# duikboot.net
KiCad netlist of a schematic drawn in EAGLE
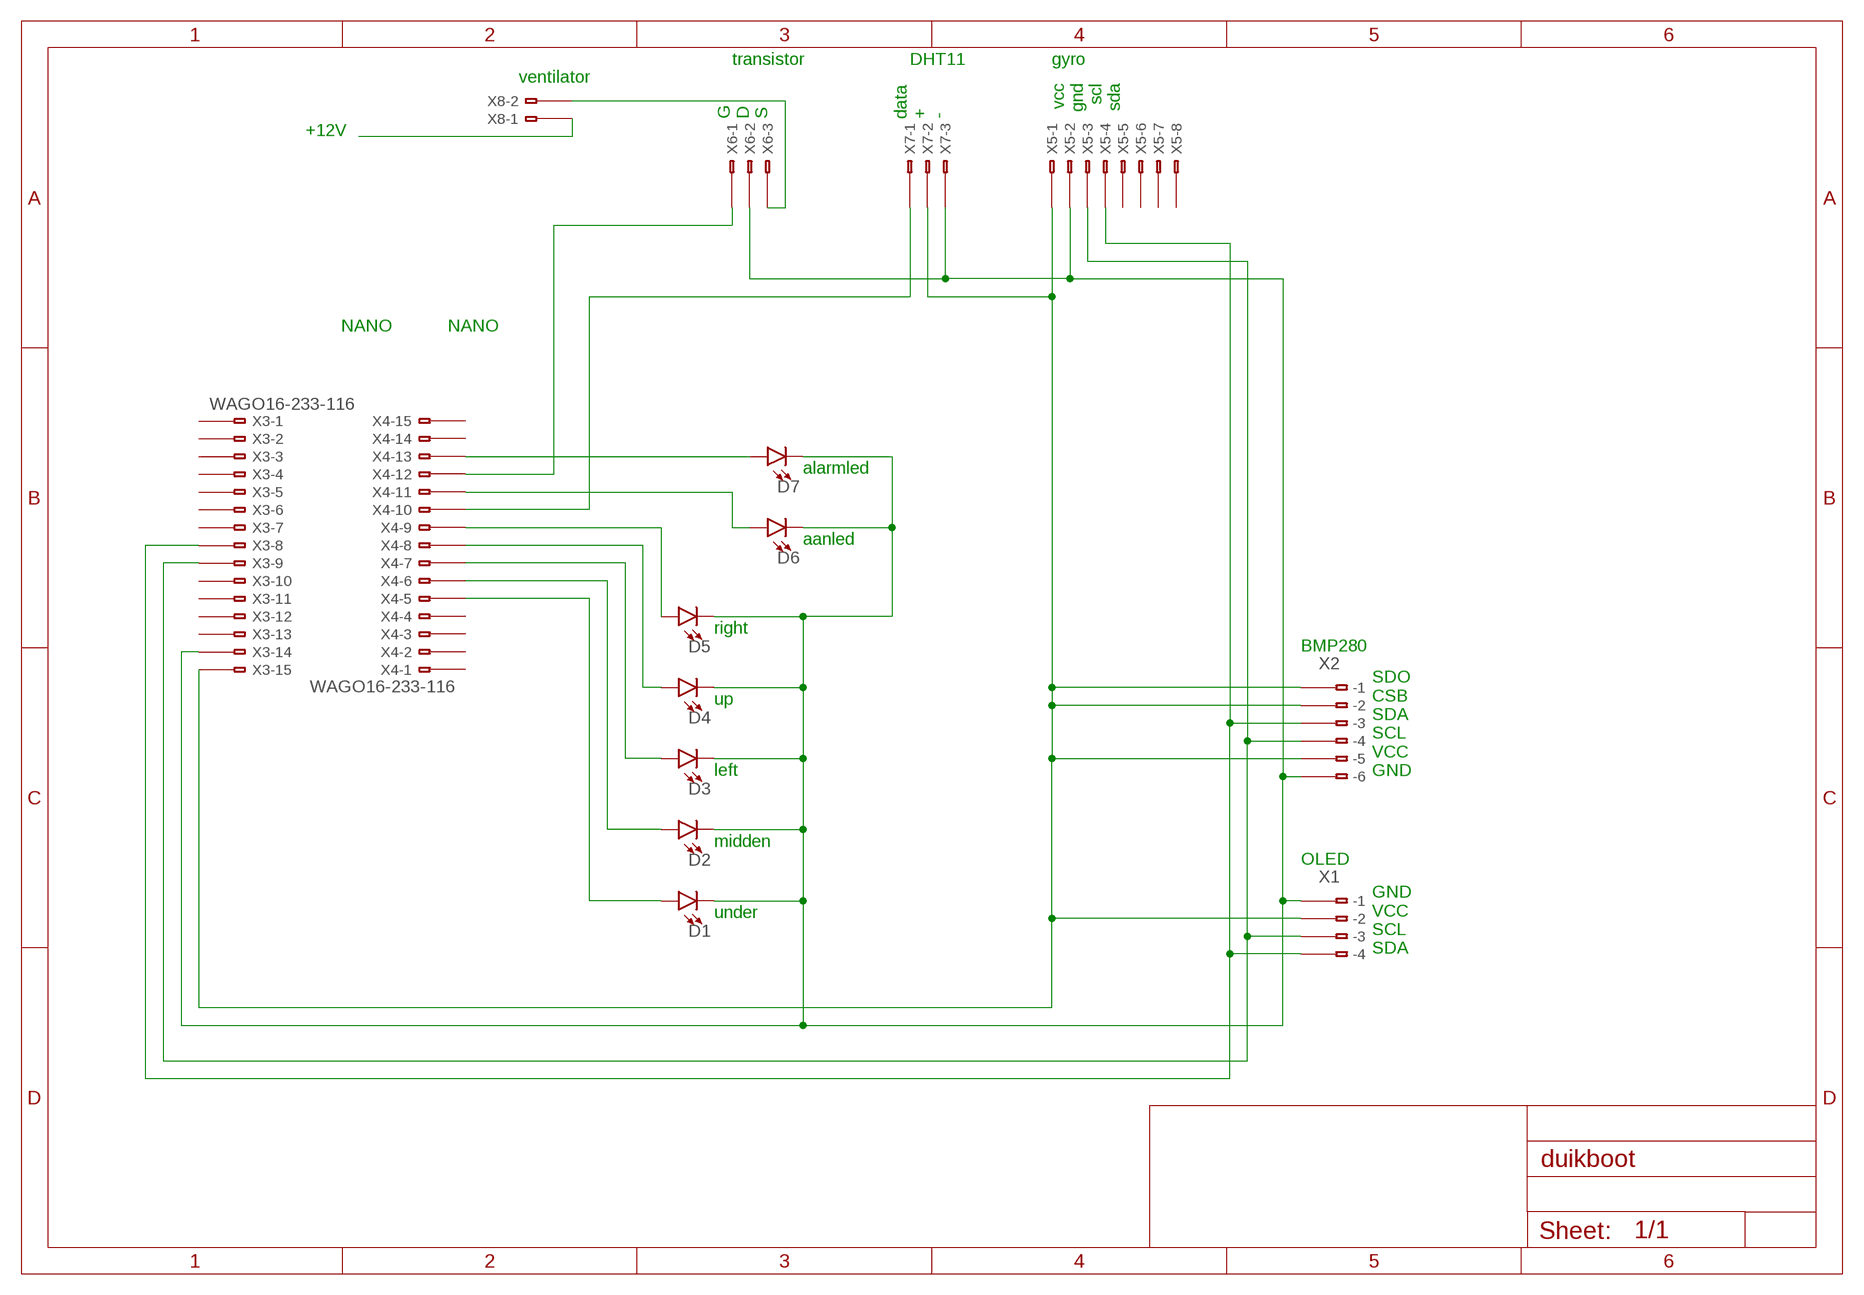
[diagram p0: schematic, sheet 1]

(export (version "E")
  (design (tool "Eeschema 10.0.6"))
  (components
    (comp (ref "D1")
      (value "LED5MM")
      (footprint "eagle-import:LED_5MM")
      (libsource (lib "eagle-import") (part "LED5MM"))
    )
    (comp (ref "D2")
      (value "LED5MM")
      (footprint "eagle-import:LED_5MM")
      (libsource (lib "eagle-import") (part "LED5MM"))
    )
    (comp (ref "D3")
      (value "LED5MM")
      (footprint "eagle-import:LED_5MM")
      (libsource (lib "eagle-import") (part "LED5MM"))
    )
    (comp (ref "D4")
      (value "LED5MM")
      (footprint "eagle-import:LED_5MM")
      (libsource (lib "eagle-import") (part "LED5MM"))
    )
    (comp (ref "D5")
      (value "LED5MM")
      (footprint "eagle-import:LED_5MM")
      (libsource (lib "eagle-import") (part "LED5MM"))
    )
    (comp (ref "D6")
      (value "LED5MM")
      (footprint "eagle-import:LED_5MM")
      (libsource (lib "eagle-import") (part "LED5MM"))
    )
    (comp (ref "D7")
      (value "LED5MM")
      (footprint "eagle-import:LED_5MM")
      (libsource (lib "eagle-import") (part "LED5MM"))
    )
    (comp (ref "X1")
      (value "233-104")
      (footprint "eagle-import:233-104")
      (libsource (lib "eagle-import") (part "233-104"))
    )
    (comp (ref "X2")
      (value "233-106")
      (footprint "eagle-import:233-106")
      (libsource (lib "eagle-import") (part "233-106"))
    )
    (comp (ref "X3")
      (value "WAGO16-233-116")
      (footprint "eagle-import:233-116")
      (fields (field (name "MPN") "233-116"))
      (libsource (lib "eagle-import") (part "WAGO16-233-116"))
    )
    (comp (ref "X4")
      (value "WAGO16-233-116")
      (footprint "eagle-import:233-116")
      (fields (field (name "MPN") "233-116"))
      (libsource (lib "eagle-import") (part "WAGO16-233-116"))
    )
    (comp (ref "X5")
      (value "WAGO16-233-116")
      (footprint "eagle-import:233-116")
      (fields (field (name "MPN") "233-116"))
      (libsource (lib "eagle-import") (part "WAGO16-233-116"))
    )
    (comp (ref "X6")
      (value "WAGO16-233-116")
      (footprint "eagle-import:233-116")
      (fields (field (name "MPN") "233-116"))
      (libsource (lib "eagle-import") (part "WAGO16-233-116"))
    )
    (comp (ref "X7")
      (value "WAGO16-233-116")
      (footprint "eagle-import:233-116")
      (fields (field (name "MPN") "233-116"))
      (libsource (lib "eagle-import") (part "WAGO16-233-116"))
    )
    (comp (ref "X8")
      (value "WAGO16-233-116")
      (footprint "eagle-import:233-116")
      (fields (field (name "MPN") "233-116"))
      (libsource (lib "eagle-import") (part "WAGO16-233-116"))
    )
  )
  (nets
    (net (code "1") (name "Net-(D1-C)") (class "Default")
      (node (ref "D1") (pin "K") (pinfunction "C_K") (pintype "passive"))
      (node (ref "D2") (pin "K") (pinfunction "C_K") (pintype "passive"))
      (node (ref "D3") (pin "K") (pinfunction "C_K") (pintype "passive"))
      (node (ref "D4") (pin "K") (pinfunction "C_K") (pintype "passive"))
      (node (ref "D5") (pin "K") (pinfunction "C_K") (pintype "passive"))
      (node (ref "D6") (pin "K") (pinfunction "C_K") (pintype "passive"))
      (node (ref "D7") (pin "K") (pinfunction "C_K") (pintype "passive"))
      (node (ref "X1") (pin "B1") (pinfunction "B-1_B1") (pintype "passive"))
      (node (ref "X2") (pin "B6") (pinfunction "B-6_B6") (pintype "passive"))
      (node (ref "X3") (pin "B14") (pinfunction "B1_B14") (pintype "passive"))
      (node (ref "X5") (pin "B2") (pinfunction "B1_B2") (pintype "passive"))
      (node (ref "X6") (pin "B2") (pinfunction "B1_B2") (pintype "passive"))
      (node (ref "X7") (pin "B3") (pinfunction "B1_B3") (pintype "passive"))
    )
    (net (code "2") (name "Net-(X1-B-2)") (class "Default")
      (node (ref "X1") (pin "B2") (pinfunction "B-2_B2") (pintype "passive"))
      (node (ref "X2") (pin "B1") (pinfunction "B-1_B1") (pintype "passive"))
      (node (ref "X2") (pin "B2") (pinfunction "B-2_B2") (pintype "passive"))
      (node (ref "X2") (pin "B5") (pinfunction "B-5_B5") (pintype "passive"))
      (node (ref "X3") (pin "B15") (pinfunction "B1_B15") (pintype "passive"))
      (node (ref "X5") (pin "B1") (pinfunction "B1_B1") (pintype "passive"))
      (node (ref "X7") (pin "B2") (pinfunction "B1_B2") (pintype "passive"))
    )
    (net (code "3") (name "Net-(X1-B-3)") (class "Default")
      (node (ref "X1") (pin "B3") (pinfunction "B-3_B3") (pintype "passive"))
      (node (ref "X2") (pin "B4") (pinfunction "B-4_B4") (pintype "passive"))
      (node (ref "X3") (pin "B9") (pinfunction "B1_B9") (pintype "passive"))
      (node (ref "X5") (pin "B3") (pinfunction "B1_B3") (pintype "passive"))
    )
    (net (code "4") (name "Net-(X1-B-4)") (class "Default")
      (node (ref "X1") (pin "B4") (pinfunction "B-4_B4") (pintype "passive"))
      (node (ref "X2") (pin "B3") (pinfunction "B-3_B3") (pintype "passive"))
      (node (ref "X3") (pin "B8") (pinfunction "B1_B8") (pintype "passive"))
      (node (ref "X5") (pin "B4") (pinfunction "B1_B4") (pintype "passive"))
    )
    (net (code "5") (name "Net-(X4B-B1)") (class "Default")
      (node (ref "X4") (pin "B10") (pinfunction "B1_B10") (pintype "passive"))
      (node (ref "X7") (pin "B1") (pinfunction "B1_B1") (pintype "passive"))
    )
    (net (code "6") (name "Net-(X4C-B1)") (class "Default")
      (node (ref "D6") (pin "A") (pinfunction "A_A") (pintype "passive"))
      (node (ref "X4") (pin "B11") (pinfunction "B1_B11") (pintype "passive"))
    )
    (net (code "7") (name "Net-(X4D-B1)") (class "Default")
      (node (ref "X4") (pin "B12") (pinfunction "B1_B12") (pintype "passive"))
      (node (ref "X6") (pin "B1") (pinfunction "B1_B1") (pintype "passive"))
    )
    (net (code "8") (name "Net-(X4E-B1)") (class "Default")
      (node (ref "D7") (pin "A") (pinfunction "A_A") (pintype "passive"))
      (node (ref "X4") (pin "B13") (pinfunction "B1_B13") (pintype "passive"))
    )
    (net (code "9") (name "Net-(X4L-B1)") (class "Default")
      (node (ref "D1") (pin "A") (pinfunction "A_A") (pintype "passive"))
      (node (ref "X4") (pin "B5") (pinfunction "B1_B5") (pintype "passive"))
    )
    (net (code "10") (name "Net-(X4M-B1)") (class "Default")
      (node (ref "D2") (pin "A") (pinfunction "A_A") (pintype "passive"))
      (node (ref "X4") (pin "B6") (pinfunction "B1_B6") (pintype "passive"))
    )
    (net (code "11") (name "Net-(X4N-B1)") (class "Default")
      (node (ref "D3") (pin "A") (pinfunction "A_A") (pintype "passive"))
      (node (ref "X4") (pin "B7") (pinfunction "B1_B7") (pintype "passive"))
    )
    (net (code "12") (name "Net-(X4O-B1)") (class "Default")
      (node (ref "D4") (pin "A") (pinfunction "A_A") (pintype "passive"))
      (node (ref "X4") (pin "B8") (pinfunction "B1_B8") (pintype "passive"))
    )
    (net (code "13") (name "Net-(X4P-B1)") (class "Default")
      (node (ref "D5") (pin "A") (pinfunction "A_A") (pintype "passive"))
      (node (ref "X4") (pin "B9") (pinfunction "B1_B9") (pintype "passive"))
    )
    (net (code "14") (name "Net-(X6J-B1)") (class "Default")
      (node (ref "X6") (pin "B3") (pinfunction "B1_B3") (pintype "passive"))
      (node (ref "X8") (pin "B2") (pinfunction "B1_B2") (pintype "passive"))
    )
    (net (code "15") (name "unconnected-(X1--1-PadA1)") (class "Default")
      (node (ref "X1") (pin "A1") (pinfunction "-1_A1") (pintype "passive"))
    )
    (net (code "16") (name "unconnected-(X1--2-PadA2)") (class "Default")
      (node (ref "X1") (pin "A2") (pinfunction "-2_A2") (pintype "passive"))
    )
    (net (code "17") (name "unconnected-(X1--3-PadA3)") (class "Default")
      (node (ref "X1") (pin "A3") (pinfunction "-3_A3") (pintype "passive"))
    )
    (net (code "18") (name "unconnected-(X1--4-PadA4)") (class "Default")
      (node (ref "X1") (pin "A4") (pinfunction "-4_A4") (pintype "passive"))
    )
    (net (code "19") (name "unconnected-(X2--1-PadA1)") (class "Default")
      (node (ref "X2") (pin "A1") (pinfunction "-1_A1") (pintype "passive"))
    )
    (net (code "20") (name "unconnected-(X2--2-PadA2)") (class "Default")
      (node (ref "X2") (pin "A2") (pinfunction "-2_A2") (pintype "passive"))
    )
    (net (code "21") (name "unconnected-(X2--3-PadA3)") (class "Default")
      (node (ref "X2") (pin "A3") (pinfunction "-3_A3") (pintype "passive"))
    )
    (net (code "22") (name "unconnected-(X2--4-PadA4)") (class "Default")
      (node (ref "X2") (pin "A4") (pinfunction "-4_A4") (pintype "passive"))
    )
    (net (code "23") (name "unconnected-(X2--5-PadA5)") (class "Default")
      (node (ref "X2") (pin "A5") (pinfunction "-5_A5") (pintype "passive"))
    )
    (net (code "24") (name "unconnected-(X2--6-PadA6)") (class "Default")
      (node (ref "X2") (pin "A6") (pinfunction "-6_A6") (pintype "passive"))
    )
    (net (code "25") (name "unconnected-(X3-PadA1)") (class "Default")
      (node (ref "X3") (pin "A1") (pinfunction "A1_A1") (pintype "passive"))
    )
    (net (code "26") (name "unconnected-(X3-PadB1)") (class "Default")
      (node (ref "X3") (pin "B1") (pinfunction "B1_B1") (pintype "passive"))
    )
    (net (code "27") (name "unconnected-(X3B-A1-PadA10)") (class "Default")
      (node (ref "X3") (pin "A10") (pinfunction "A1_A10") (pintype "passive"))
    )
    (net (code "28") (name "unconnected-(X3B-B1-PadB10)") (class "Default")
      (node (ref "X3") (pin "B10") (pinfunction "B1_B10") (pintype "passive"))
    )
    (net (code "29") (name "unconnected-(X3C-A1-PadA11)") (class "Default")
      (node (ref "X3") (pin "A11") (pinfunction "A1_A11") (pintype "passive"))
    )
    (net (code "30") (name "unconnected-(X3C-B1-PadB11)") (class "Default")
      (node (ref "X3") (pin "B11") (pinfunction "B1_B11") (pintype "passive"))
    )
    (net (code "31") (name "unconnected-(X3D-A1-PadA12)") (class "Default")
      (node (ref "X3") (pin "A12") (pinfunction "A1_A12") (pintype "passive"))
    )
    (net (code "32") (name "unconnected-(X3D-B1-PadB12)") (class "Default")
      (node (ref "X3") (pin "B12") (pinfunction "B1_B12") (pintype "passive"))
    )
    (net (code "33") (name "unconnected-(X3E-A1-PadA13)") (class "Default")
      (node (ref "X3") (pin "A13") (pinfunction "A1_A13") (pintype "passive"))
    )
    (net (code "34") (name "unconnected-(X3E-B1-PadB13)") (class "Default")
      (node (ref "X3") (pin "B13") (pinfunction "B1_B13") (pintype "passive"))
    )
    (net (code "35") (name "unconnected-(X3F-A1-PadA14)") (class "Default")
      (node (ref "X3") (pin "A14") (pinfunction "A1_A14") (pintype "passive"))
    )
    (net (code "36") (name "unconnected-(X3G-A1-PadA15)") (class "Default")
      (node (ref "X3") (pin "A15") (pinfunction "A1_A15") (pintype "passive"))
    )
    (net (code "37") (name "unconnected-(X3I-A1-PadA2)") (class "Default")
      (node (ref "X3") (pin "A2") (pinfunction "A1_A2") (pintype "passive"))
    )
    (net (code "38") (name "unconnected-(X3I-B1-PadB2)") (class "Default")
      (node (ref "X3") (pin "B2") (pinfunction "B1_B2") (pintype "passive"))
    )
    (net (code "39") (name "unconnected-(X3J-A1-PadA3)") (class "Default")
      (node (ref "X3") (pin "A3") (pinfunction "A1_A3") (pintype "passive"))
    )
    (net (code "40") (name "unconnected-(X3J-B1-PadB3)") (class "Default")
      (node (ref "X3") (pin "B3") (pinfunction "B1_B3") (pintype "passive"))
    )
    (net (code "41") (name "unconnected-(X3K-A1-PadA4)") (class "Default")
      (node (ref "X3") (pin "A4") (pinfunction "A1_A4") (pintype "passive"))
    )
    (net (code "42") (name "unconnected-(X3K-B1-PadB4)") (class "Default")
      (node (ref "X3") (pin "B4") (pinfunction "B1_B4") (pintype "passive"))
    )
    (net (code "43") (name "unconnected-(X3L-A1-PadA5)") (class "Default")
      (node (ref "X3") (pin "A5") (pinfunction "A1_A5") (pintype "passive"))
    )
    (net (code "44") (name "unconnected-(X3L-B1-PadB5)") (class "Default")
      (node (ref "X3") (pin "B5") (pinfunction "B1_B5") (pintype "passive"))
    )
    (net (code "45") (name "unconnected-(X3M-A1-PadA6)") (class "Default")
      (node (ref "X3") (pin "A6") (pinfunction "A1_A6") (pintype "passive"))
    )
    (net (code "46") (name "unconnected-(X3M-B1-PadB6)") (class "Default")
      (node (ref "X3") (pin "B6") (pinfunction "B1_B6") (pintype "passive"))
    )
    (net (code "47") (name "unconnected-(X3N-A1-PadA7)") (class "Default")
      (node (ref "X3") (pin "A7") (pinfunction "A1_A7") (pintype "passive"))
    )
    (net (code "48") (name "unconnected-(X3N-B1-PadB7)") (class "Default")
      (node (ref "X3") (pin "B7") (pinfunction "B1_B7") (pintype "passive"))
    )
    (net (code "49") (name "unconnected-(X3O-A1-PadA8)") (class "Default")
      (node (ref "X3") (pin "A8") (pinfunction "A1_A8") (pintype "passive"))
    )
    (net (code "50") (name "unconnected-(X3P-A1-PadA9)") (class "Default")
      (node (ref "X3") (pin "A9") (pinfunction "A1_A9") (pintype "passive"))
    )
    (net (code "51") (name "unconnected-(X4-PadA1)") (class "Default")
      (node (ref "X4") (pin "A1") (pinfunction "A1_A1") (pintype "passive"))
    )
    (net (code "52") (name "unconnected-(X4-PadB1)") (class "Default")
      (node (ref "X4") (pin "B1") (pinfunction "B1_B1") (pintype "passive"))
    )
    (net (code "53") (name "unconnected-(X4B-A1-PadA10)") (class "Default")
      (node (ref "X4") (pin "A10") (pinfunction "A1_A10") (pintype "passive"))
    )
    (net (code "54") (name "unconnected-(X4C-A1-PadA11)") (class "Default")
      (node (ref "X4") (pin "A11") (pinfunction "A1_A11") (pintype "passive"))
    )
    (net (code "55") (name "unconnected-(X4D-A1-PadA12)") (class "Default")
      (node (ref "X4") (pin "A12") (pinfunction "A1_A12") (pintype "passive"))
    )
    (net (code "56") (name "unconnected-(X4E-A1-PadA13)") (class "Default")
      (node (ref "X4") (pin "A13") (pinfunction "A1_A13") (pintype "passive"))
    )
    (net (code "57") (name "unconnected-(X4F-A1-PadA14)") (class "Default")
      (node (ref "X4") (pin "A14") (pinfunction "A1_A14") (pintype "passive"))
    )
    (net (code "58") (name "unconnected-(X4F-B1-PadB14)") (class "Default")
      (node (ref "X4") (pin "B14") (pinfunction "B1_B14") (pintype "passive"))
    )
    (net (code "59") (name "unconnected-(X4G-A1-PadA15)") (class "Default")
      (node (ref "X4") (pin "A15") (pinfunction "A1_A15") (pintype "passive"))
    )
    (net (code "60") (name "unconnected-(X4G-B1-PadB15)") (class "Default")
      (node (ref "X4") (pin "B15") (pinfunction "B1_B15") (pintype "passive"))
    )
    (net (code "61") (name "unconnected-(X4I-A1-PadA2)") (class "Default")
      (node (ref "X4") (pin "A2") (pinfunction "A1_A2") (pintype "passive"))
    )
    (net (code "62") (name "unconnected-(X4I-B1-PadB2)") (class "Default")
      (node (ref "X4") (pin "B2") (pinfunction "B1_B2") (pintype "passive"))
    )
    (net (code "63") (name "unconnected-(X4J-A1-PadA3)") (class "Default")
      (node (ref "X4") (pin "A3") (pinfunction "A1_A3") (pintype "passive"))
    )
    (net (code "64") (name "unconnected-(X4J-B1-PadB3)") (class "Default")
      (node (ref "X4") (pin "B3") (pinfunction "B1_B3") (pintype "passive"))
    )
    (net (code "65") (name "unconnected-(X4K-A1-PadA4)") (class "Default")
      (node (ref "X4") (pin "A4") (pinfunction "A1_A4") (pintype "passive"))
    )
    (net (code "66") (name "unconnected-(X4K-B1-PadB4)") (class "Default")
      (node (ref "X4") (pin "B4") (pinfunction "B1_B4") (pintype "passive"))
    )
    (net (code "67") (name "unconnected-(X4L-A1-PadA5)") (class "Default")
      (node (ref "X4") (pin "A5") (pinfunction "A1_A5") (pintype "passive"))
    )
    (net (code "68") (name "unconnected-(X4M-A1-PadA6)") (class "Default")
      (node (ref "X4") (pin "A6") (pinfunction "A1_A6") (pintype "passive"))
    )
    (net (code "69") (name "unconnected-(X4N-A1-PadA7)") (class "Default")
      (node (ref "X4") (pin "A7") (pinfunction "A1_A7") (pintype "passive"))
    )
    (net (code "70") (name "unconnected-(X4O-A1-PadA8)") (class "Default")
      (node (ref "X4") (pin "A8") (pinfunction "A1_A8") (pintype "passive"))
    )
    (net (code "71") (name "unconnected-(X4P-A1-PadA9)") (class "Default")
      (node (ref "X4") (pin "A9") (pinfunction "A1_A9") (pintype "passive"))
    )
    (net (code "72") (name "unconnected-(X5-PadA1)") (class "Default")
      (node (ref "X5") (pin "A1") (pinfunction "A1_A1") (pintype "passive"))
    )
    (net (code "73") (name "unconnected-(X5I-A1-PadA2)") (class "Default")
      (node (ref "X5") (pin "A2") (pinfunction "A1_A2") (pintype "passive"))
    )
    (net (code "74") (name "unconnected-(X5J-A1-PadA3)") (class "Default")
      (node (ref "X5") (pin "A3") (pinfunction "A1_A3") (pintype "passive"))
    )
    (net (code "75") (name "unconnected-(X5K-A1-PadA4)") (class "Default")
      (node (ref "X5") (pin "A4") (pinfunction "A1_A4") (pintype "passive"))
    )
    (net (code "76") (name "unconnected-(X5L-A1-PadA5)") (class "Default")
      (node (ref "X5") (pin "A5") (pinfunction "A1_A5") (pintype "passive"))
    )
    (net (code "77") (name "unconnected-(X5L-B1-PadB5)") (class "Default")
      (node (ref "X5") (pin "B5") (pinfunction "B1_B5") (pintype "passive"))
    )
    (net (code "78") (name "unconnected-(X5M-A1-PadA6)") (class "Default")
      (node (ref "X5") (pin "A6") (pinfunction "A1_A6") (pintype "passive"))
    )
    (net (code "79") (name "unconnected-(X5M-B1-PadB6)") (class "Default")
      (node (ref "X5") (pin "B6") (pinfunction "B1_B6") (pintype "passive"))
    )
    (net (code "80") (name "unconnected-(X5N-A1-PadA7)") (class "Default")
      (node (ref "X5") (pin "A7") (pinfunction "A1_A7") (pintype "passive"))
    )
    (net (code "81") (name "unconnected-(X5N-B1-PadB7)") (class "Default")
      (node (ref "X5") (pin "B7") (pinfunction "B1_B7") (pintype "passive"))
    )
    (net (code "82") (name "unconnected-(X5O-A1-PadA8)") (class "Default")
      (node (ref "X5") (pin "A8") (pinfunction "A1_A8") (pintype "passive"))
    )
    (net (code "83") (name "unconnected-(X5O-B1-PadB8)") (class "Default")
      (node (ref "X5") (pin "B8") (pinfunction "B1_B8") (pintype "passive"))
    )
    (net (code "84") (name "unconnected-(X6-PadA1)") (class "Default")
      (node (ref "X6") (pin "A1") (pinfunction "A1_A1") (pintype "passive"))
    )
    (net (code "85") (name "unconnected-(X6I-A1-PadA2)") (class "Default")
      (node (ref "X6") (pin "A2") (pinfunction "A1_A2") (pintype "passive"))
    )
    (net (code "86") (name "unconnected-(X6J-A1-PadA3)") (class "Default")
      (node (ref "X6") (pin "A3") (pinfunction "A1_A3") (pintype "passive"))
    )
    (net (code "87") (name "unconnected-(X7-PadA1)") (class "Default")
      (node (ref "X7") (pin "A1") (pinfunction "A1_A1") (pintype "passive"))
    )
    (net (code "88") (name "unconnected-(X7I-A1-PadA2)") (class "Default")
      (node (ref "X7") (pin "A2") (pinfunction "A1_A2") (pintype "passive"))
    )
    (net (code "89") (name "unconnected-(X7J-A1-PadA3)") (class "Default")
      (node (ref "X7") (pin "A3") (pinfunction "A1_A3") (pintype "passive"))
    )
    (net (code "90") (name "unconnected-(X8-PadA1)") (class "Default")
      (node (ref "X8") (pin "A1") (pinfunction "A1_A1") (pintype "passive"))
    )
    (net (code "91") (name "unconnected-(X8-PadB1)") (class "Default")
      (node (ref "X8") (pin "B1") (pinfunction "B1_B1") (pintype "passive"))
    )
    (net (code "92") (name "unconnected-(X8I-A1-PadA2)") (class "Default")
      (node (ref "X8") (pin "A2") (pinfunction "A1_A2") (pintype "passive"))
    )
  )
)
